# I2C_PinOut.net
KiCad netlist of a schematic drawn in Altium Designer
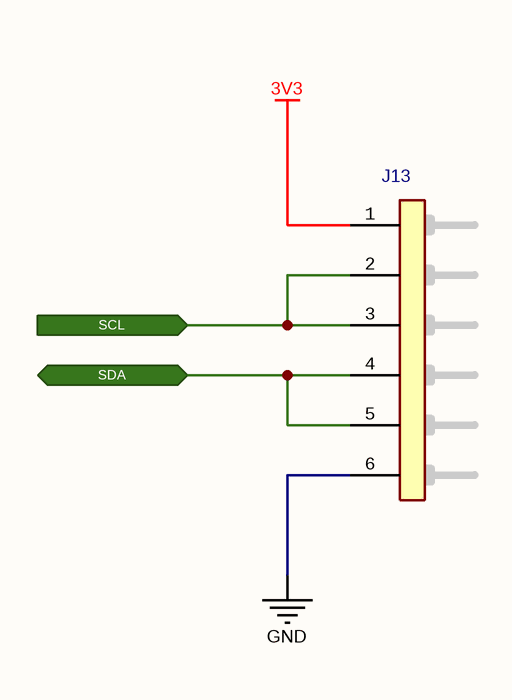
[diagram p0: I2C PinOut.SchDoc]

(export (version "E")
  (design (tool "Eeschema 10.0.6"))
  (components
    (comp (ref "J13")
      (value "2.54 mm Pitch 6P Male Connector")
      (footprint "6P Header")
      (description "Headers & Wire Housings BREAKAWAY HDR VERT 6")
      (fields
        (field (name "MANUFACTURER PART NUMBER") "22-28-4063")
        (field (name "MOUSER PART NUMBER") "538-22-28-4063")
      )
      (libsource (lib "Ovoo_Library") (part "Connector - Male Header 6P (2.54)"))
    )
  )
  (nets
    (net (code "1") (name "/SCL") (class "Default")
      (node (ref "J13") (pin "2") (pinfunction "Pin-2_2") (pintype "passive"))
      (node (ref "J13") (pin "3") (pinfunction "Pin-3_3") (pintype "passive"))
    )
    (net (code "2") (name "/SDA") (class "Default")
      (node (ref "J13") (pin "4") (pinfunction "Pin-4_4") (pintype "passive"))
      (node (ref "J13") (pin "5") (pinfunction "Pin-5_5") (pintype "passive"))
    )
    (net (code "3") (name "3V3") (class "Default")
      (node (ref "J13") (pin "1") (pinfunction "Pin-1_1") (pintype "passive"))
    )
    (net (code "4") (name "GND") (class "Default")
      (node (ref "J13") (pin "6") (pinfunction "Pin-6_6") (pintype "passive"))
    )
  )
)
